# io1.net
KiCad netlist of a schematic drawn in EAGLE
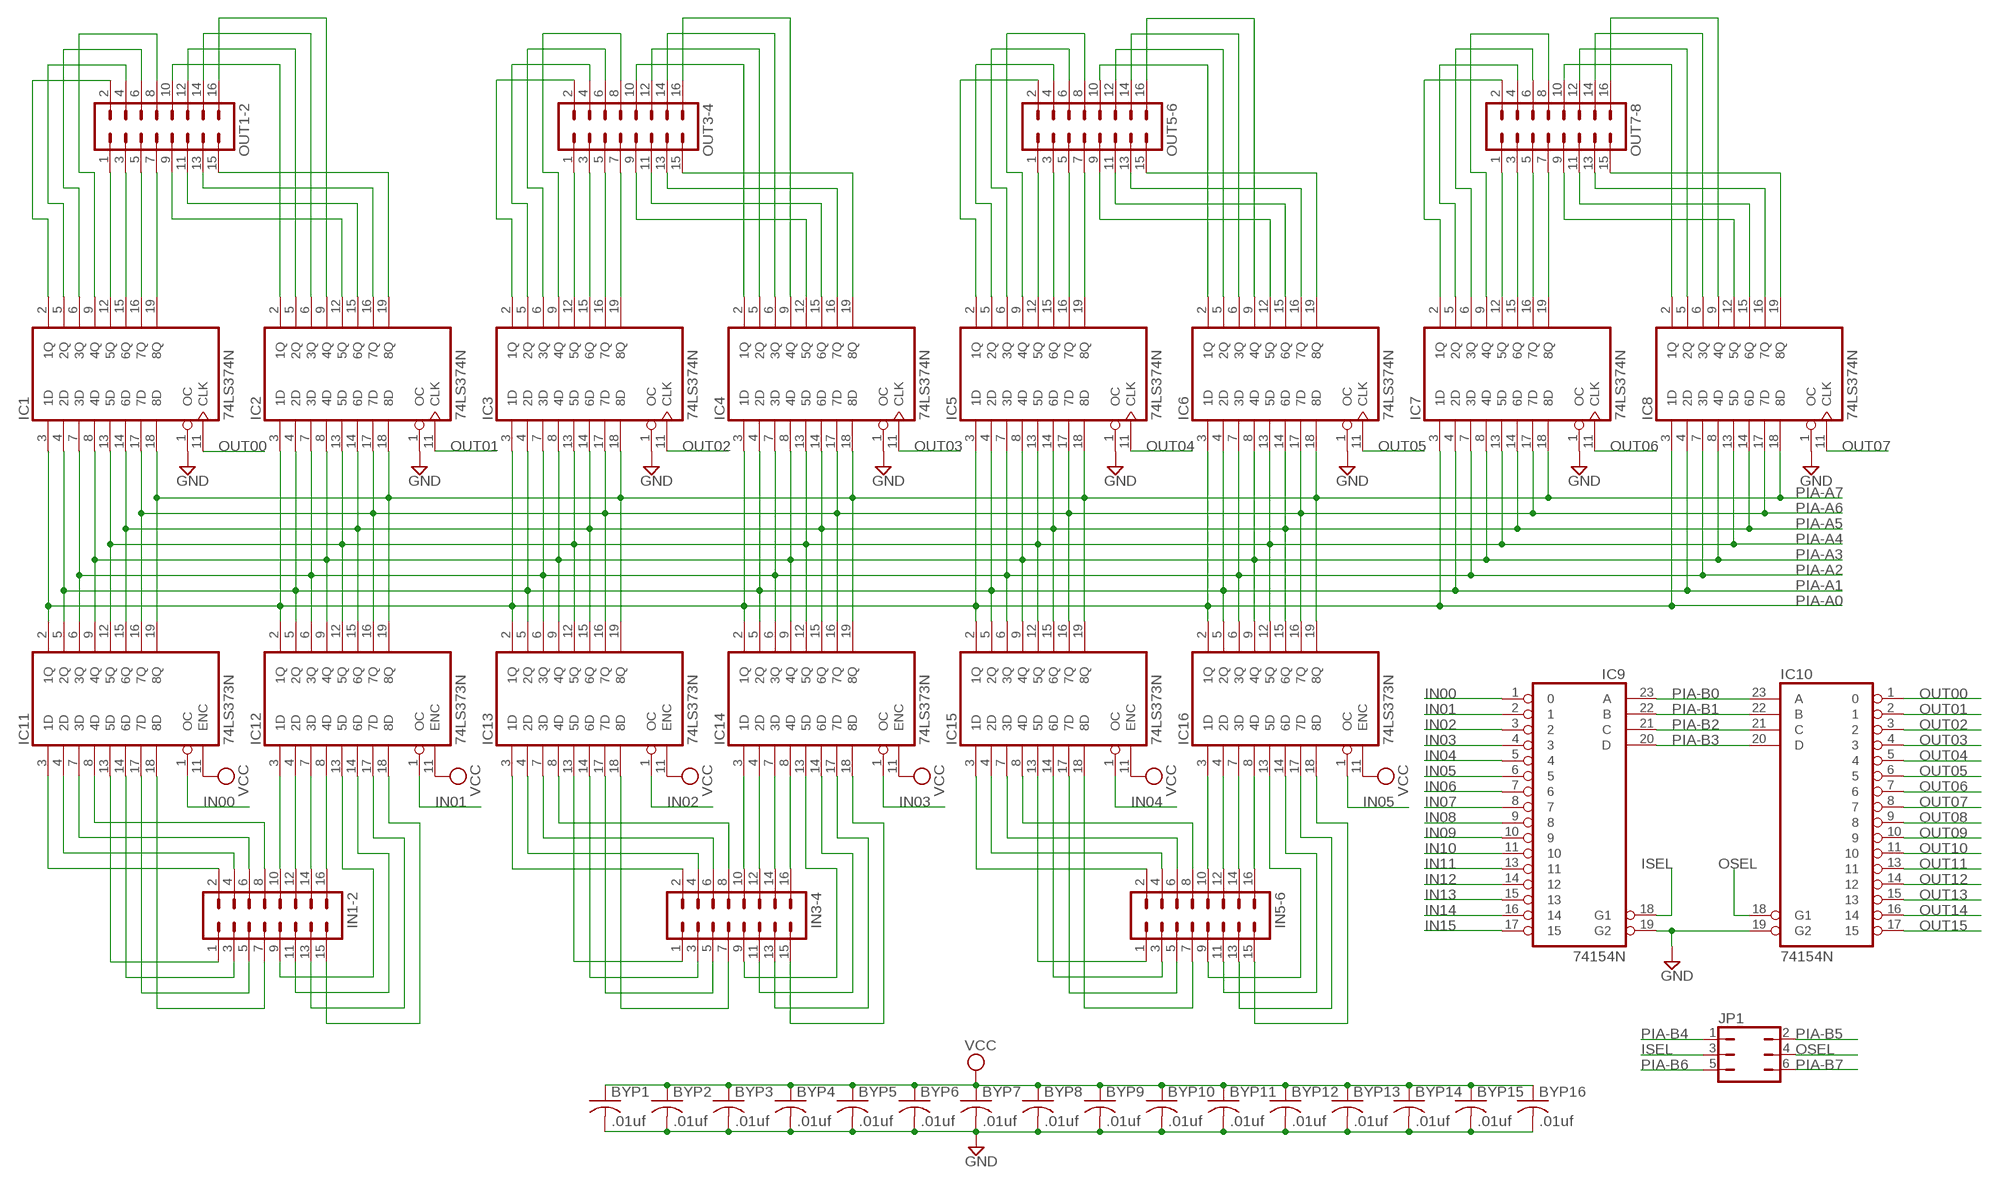
[diagram p0: schematic, sheet 1]
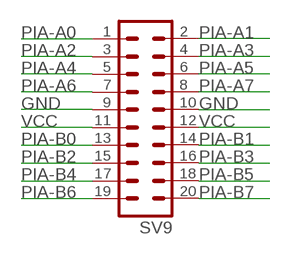
[diagram p1: schematic, sheet 2]

(export (version "E")
  (design (tool "Eeschema 10.0.6"))
  (components
    (comp (ref "SV9")
      (value "MA10-2")
      (footprint "eagle-import:MA10-2")
      (libsource (lib "eagle-import") (part "MA10-2"))
    )
    (comp (ref "BYP1")
      (value ".01uf")
      (footprint "eagle-import:C050-025X075")
      (libsource (lib "eagle-import") (part "C-US050-025X075"))
    )
    (comp (ref "BYP2")
      (value ".01uf")
      (footprint "eagle-import:C050-025X075")
      (libsource (lib "eagle-import") (part "C-US050-025X075"))
    )
    (comp (ref "BYP3")
      (value ".01uf")
      (footprint "eagle-import:C050-025X075")
      (libsource (lib "eagle-import") (part "C-US050-025X075"))
    )
    (comp (ref "BYP4")
      (value ".01uf")
      (footprint "eagle-import:C050-025X075")
      (libsource (lib "eagle-import") (part "C-US050-025X075"))
    )
    (comp (ref "BYP5")
      (value ".01uf")
      (footprint "eagle-import:C050-025X075")
      (libsource (lib "eagle-import") (part "C-US050-025X075"))
    )
    (comp (ref "BYP6")
      (value ".01uf")
      (footprint "eagle-import:C050-025X075")
      (libsource (lib "eagle-import") (part "C-US050-025X075"))
    )
    (comp (ref "BYP7")
      (value ".01uf")
      (footprint "eagle-import:C050-025X075")
      (libsource (lib "eagle-import") (part "C-US050-025X075"))
    )
    (comp (ref "BYP8")
      (value ".01uf")
      (footprint "eagle-import:C050-025X075")
      (libsource (lib "eagle-import") (part "C-US050-025X075"))
    )
    (comp (ref "BYP9")
      (value ".01uf")
      (footprint "eagle-import:C050-025X075")
      (libsource (lib "eagle-import") (part "C-US050-025X075"))
    )
    (comp (ref "BYP10")
      (value ".01uf")
      (footprint "eagle-import:C050-025X075")
      (libsource (lib "eagle-import") (part "C-US050-025X075"))
    )
    (comp (ref "BYP11")
      (value ".01uf")
      (footprint "eagle-import:C050-025X075")
      (libsource (lib "eagle-import") (part "C-US050-025X075"))
    )
    (comp (ref "BYP12")
      (value ".01uf")
      (footprint "eagle-import:C050-025X075")
      (libsource (lib "eagle-import") (part "C-US050-025X075"))
    )
    (comp (ref "BYP13")
      (value ".01uf")
      (footprint "eagle-import:C050-025X075")
      (libsource (lib "eagle-import") (part "C-US050-025X075"))
    )
    (comp (ref "BYP14")
      (value ".01uf")
      (footprint "eagle-import:C050-025X075")
      (libsource (lib "eagle-import") (part "C-US050-025X075"))
    )
    (comp (ref "BYP15")
      (value ".01uf")
      (footprint "eagle-import:C050-025X075")
      (libsource (lib "eagle-import") (part "C-US050-025X075"))
    )
    (comp (ref "BYP16")
      (value ".01uf")
      (footprint "eagle-import:C050-025X075")
      (libsource (lib "eagle-import") (part "C-US050-025X075"))
    )
    (comp (ref "IC1")
      (value "74LS374N")
      (footprint "eagle-import:DIL20")
      (libsource (lib "eagle-import") (part "74374NLS"))
    )
    (comp (ref "IC2")
      (value "74LS374N")
      (footprint "eagle-import:DIL20")
      (libsource (lib "eagle-import") (part "74374NLS"))
    )
    (comp (ref "IC3")
      (value "74LS374N")
      (footprint "eagle-import:DIL20")
      (libsource (lib "eagle-import") (part "74374NLS"))
    )
    (comp (ref "IC4")
      (value "74LS374N")
      (footprint "eagle-import:DIL20")
      (libsource (lib "eagle-import") (part "74374NLS"))
    )
    (comp (ref "IC5")
      (value "74LS374N")
      (footprint "eagle-import:DIL20")
      (libsource (lib "eagle-import") (part "74374NLS"))
    )
    (comp (ref "IC6")
      (value "74LS374N")
      (footprint "eagle-import:DIL20")
      (libsource (lib "eagle-import") (part "74374NLS"))
    )
    (comp (ref "IC7")
      (value "74LS374N")
      (footprint "eagle-import:DIL20")
      (libsource (lib "eagle-import") (part "74374NLS"))
    )
    (comp (ref "IC8")
      (value "74LS374N")
      (footprint "eagle-import:DIL20")
      (libsource (lib "eagle-import") (part "74374NLS"))
    )
    (comp (ref "IC9")
      (value "74154N")
      (footprint "eagle-import:DIL24-6")
      (libsource (lib "eagle-import") (part "74154N"))
    )
    (comp (ref "IC10")
      (value "74154N")
      (footprint "eagle-import:DIL24-6")
      (libsource (lib "eagle-import") (part "74154N"))
    )
    (comp (ref "IC11")
      (value "74LS373N")
      (footprint "eagle-import:DIL20")
      (libsource (lib "eagle-import") (part "74373NLS"))
    )
    (comp (ref "IC12")
      (value "74LS373N")
      (footprint "eagle-import:DIL20")
      (libsource (lib "eagle-import") (part "74373NLS"))
    )
    (comp (ref "IC13")
      (value "74LS373N")
      (footprint "eagle-import:DIL20")
      (libsource (lib "eagle-import") (part "74373NLS"))
    )
    (comp (ref "IC14")
      (value "74LS373N")
      (footprint "eagle-import:DIL20")
      (libsource (lib "eagle-import") (part "74373NLS"))
    )
    (comp (ref "IC15")
      (value "74LS373N")
      (footprint "eagle-import:DIL20")
      (libsource (lib "eagle-import") (part "74373NLS"))
    )
    (comp (ref "IC16")
      (value "74LS373N")
      (footprint "eagle-import:DIL20")
      (libsource (lib "eagle-import") (part "74373NLS"))
    )
    (comp (ref "IN1-2")
      (value "MA08-2")
      (footprint "eagle-import:MA08-2")
      (libsource (lib "eagle-import") (part "MA08-2"))
    )
    (comp (ref "IN3-4")
      (value "MA08-2")
      (footprint "eagle-import:MA08-2")
      (libsource (lib "eagle-import") (part "MA08-2"))
    )
    (comp (ref "IN5-6")
      (value "MA08-2")
      (footprint "eagle-import:MA08-2")
      (libsource (lib "eagle-import") (part "MA08-2"))
    )
    (comp (ref "JP1")
      (value "JP3Q")
      (footprint "eagle-import:JP3Q")
      (libsource (lib "eagle-import") (part "JP3Q"))
    )
    (comp (ref "OUT1-2")
      (value "MA08-2")
      (footprint "eagle-import:MA08-2")
      (libsource (lib "eagle-import") (part "MA08-2"))
    )
    (comp (ref "OUT3-4")
      (value "MA08-2")
      (footprint "eagle-import:MA08-2")
      (libsource (lib "eagle-import") (part "MA08-2"))
    )
    (comp (ref "OUT5-6")
      (value "MA08-2")
      (footprint "eagle-import:MA08-2")
      (libsource (lib "eagle-import") (part "MA08-2"))
    )
    (comp (ref "OUT7-8")
      (value "MA08-2")
      (footprint "eagle-import:MA08-2")
      (libsource (lib "eagle-import") (part "MA08-2"))
    )
  )
  (nets
    (net (code "1") (name "GND") (class "Default")
      (node (ref "BYP1") (pin "2") (pinfunction "2_2") (pintype "passive"))
      (node (ref "BYP10") (pin "2") (pinfunction "2_2") (pintype "passive"))
      (node (ref "BYP11") (pin "2") (pinfunction "2_2") (pintype "passive"))
      (node (ref "BYP12") (pin "2") (pinfunction "2_2") (pintype "passive"))
      (node (ref "BYP13") (pin "2") (pinfunction "2_2") (pintype "passive"))
      (node (ref "BYP14") (pin "2") (pinfunction "2_2") (pintype "passive"))
      (node (ref "BYP15") (pin "2") (pinfunction "2_2") (pintype "passive"))
      (node (ref "BYP16") (pin "2") (pinfunction "2_2") (pintype "passive"))
      (node (ref "BYP2") (pin "2") (pinfunction "2_2") (pintype "passive"))
      (node (ref "BYP3") (pin "2") (pinfunction "2_2") (pintype "passive"))
      (node (ref "BYP4") (pin "2") (pinfunction "2_2") (pintype "passive"))
      (node (ref "BYP5") (pin "2") (pinfunction "2_2") (pintype "passive"))
      (node (ref "BYP6") (pin "2") (pinfunction "2_2") (pintype "passive"))
      (node (ref "BYP7") (pin "2") (pinfunction "2_2") (pintype "passive"))
      (node (ref "BYP8") (pin "2") (pinfunction "2_2") (pintype "passive"))
      (node (ref "BYP9") (pin "2") (pinfunction "2_2") (pintype "passive"))
      (node (ref "IC1") (pin "1") (pinfunction "OC_1") (pintype "input"))
      (node (ref "IC10") (pin "19") (pinfunction "G2_19") (pintype "input"))
      (node (ref "IC2") (pin "1") (pinfunction "OC_1") (pintype "input"))
      (node (ref "IC3") (pin "1") (pinfunction "OC_1") (pintype "input"))
      (node (ref "IC4") (pin "1") (pinfunction "OC_1") (pintype "input"))
      (node (ref "IC5") (pin "1") (pinfunction "OC_1") (pintype "input"))
      (node (ref "IC6") (pin "1") (pinfunction "OC_1") (pintype "input"))
      (node (ref "IC7") (pin "1") (pinfunction "OC_1") (pintype "input"))
      (node (ref "IC8") (pin "1") (pinfunction "OC_1") (pintype "input"))
      (node (ref "IC9") (pin "19") (pinfunction "G2_19") (pintype "input"))
      (node (ref "SV9") (pin "10") (pinfunction "10_10") (pintype "passive"))
      (node (ref "SV9") (pin "9") (pinfunction "9_9") (pintype "passive"))
    )
    (net (code "2") (name "IN00") (class "Default")
      (node (ref "IC11") (pin "1") (pinfunction "OC_1") (pintype "input"))
      (node (ref "IC9") (pin "1") (pinfunction "0_1") (pintype "output"))
    )
    (net (code "3") (name "IN01") (class "Default")
      (node (ref "IC12") (pin "1") (pinfunction "OC_1") (pintype "input"))
      (node (ref "IC9") (pin "2") (pinfunction "1_2") (pintype "output"))
    )
    (net (code "4") (name "IN02") (class "Default")
      (node (ref "IC13") (pin "1") (pinfunction "OC_1") (pintype "input"))
      (node (ref "IC9") (pin "3") (pinfunction "2_3") (pintype "output"))
    )
    (net (code "5") (name "IN03") (class "Default")
      (node (ref "IC14") (pin "1") (pinfunction "OC_1") (pintype "input"))
      (node (ref "IC9") (pin "4") (pinfunction "3_4") (pintype "output"))
    )
    (net (code "6") (name "IN04") (class "Default")
      (node (ref "IC15") (pin "1") (pinfunction "OC_1") (pintype "input"))
      (node (ref "IC9") (pin "5") (pinfunction "4_5") (pintype "output"))
    )
    (net (code "7") (name "IN05") (class "Default")
      (node (ref "IC16") (pin "1") (pinfunction "OC_1") (pintype "input"))
      (node (ref "IC9") (pin "6") (pinfunction "5_6") (pintype "output"))
    )
    (net (code "8") (name "IN06") (class "Default")
      (node (ref "IC9") (pin "7") (pinfunction "6_7") (pintype "output"))
    )
    (net (code "9") (name "IN07") (class "Default")
      (node (ref "IC9") (pin "8") (pinfunction "7_8") (pintype "output"))
    )
    (net (code "10") (name "IN08") (class "Default")
      (node (ref "IC9") (pin "9") (pinfunction "8_9") (pintype "output"))
    )
    (net (code "11") (name "IN09") (class "Default")
      (node (ref "IC9") (pin "10") (pinfunction "9_10") (pintype "output"))
    )
    (net (code "12") (name "IN10") (class "Default")
      (node (ref "IC9") (pin "11") (pinfunction "10_11") (pintype "output"))
    )
    (net (code "13") (name "IN11") (class "Default")
      (node (ref "IC9") (pin "13") (pinfunction "11_13") (pintype "output"))
    )
    (net (code "14") (name "IN12") (class "Default")
      (node (ref "IC9") (pin "14") (pinfunction "12_14") (pintype "output"))
    )
    (net (code "15") (name "IN13") (class "Default")
      (node (ref "IC9") (pin "15") (pinfunction "13_15") (pintype "output"))
    )
    (net (code "16") (name "IN14") (class "Default")
      (node (ref "IC9") (pin "16") (pinfunction "14_16") (pintype "output"))
    )
    (net (code "17") (name "IN15") (class "Default")
      (node (ref "IC9") (pin "17") (pinfunction "15_17") (pintype "output"))
    )
    (net (code "18") (name "ISEL") (class "Default")
      (node (ref "IC9") (pin "18") (pinfunction "G1_18") (pintype "input"))
      (node (ref "JP1") (pin "3") (pinfunction "3_3") (pintype "passive"))
    )
    (net (code "19") (name "Net-(IC1A-1Q)") (class "Default")
      (node (ref "IC1") (pin "2") (pinfunction "1Q_2") (pintype "tri_state"))
      (node (ref "OUT1-2") (pin "2") (pinfunction "2_2") (pintype "passive"))
    )
    (net (code "20") (name "Net-(IC1A-2Q)") (class "Default")
      (node (ref "IC1") (pin "5") (pinfunction "2Q_5") (pintype "tri_state"))
      (node (ref "OUT1-2") (pin "4") (pinfunction "4_4") (pintype "passive"))
    )
    (net (code "21") (name "Net-(IC1A-3Q)") (class "Default")
      (node (ref "IC1") (pin "6") (pinfunction "3Q_6") (pintype "tri_state"))
      (node (ref "OUT1-2") (pin "6") (pinfunction "6_6") (pintype "passive"))
    )
    (net (code "22") (name "Net-(IC1A-4Q)") (class "Default")
      (node (ref "IC1") (pin "9") (pinfunction "4Q_9") (pintype "tri_state"))
      (node (ref "OUT1-2") (pin "8") (pinfunction "8_8") (pintype "passive"))
    )
    (net (code "23") (name "Net-(IC1A-5Q)") (class "Default")
      (node (ref "IC1") (pin "12") (pinfunction "5Q_12") (pintype "tri_state"))
      (node (ref "OUT1-2") (pin "1") (pinfunction "1_1") (pintype "passive"))
    )
    (net (code "24") (name "Net-(IC1A-6Q)") (class "Default")
      (node (ref "IC1") (pin "15") (pinfunction "6Q_15") (pintype "tri_state"))
      (node (ref "OUT1-2") (pin "3") (pinfunction "3_3") (pintype "passive"))
    )
    (net (code "25") (name "Net-(IC1A-7Q)") (class "Default")
      (node (ref "IC1") (pin "16") (pinfunction "7Q_16") (pintype "tri_state"))
      (node (ref "OUT1-2") (pin "5") (pinfunction "5_5") (pintype "passive"))
    )
    (net (code "26") (name "Net-(IC1A-8Q)") (class "Default")
      (node (ref "IC1") (pin "19") (pinfunction "8Q_19") (pintype "tri_state"))
      (node (ref "OUT1-2") (pin "7") (pinfunction "7_7") (pintype "passive"))
    )
    (net (code "27") (name "Net-(IC2A-1Q)") (class "Default")
      (node (ref "IC2") (pin "2") (pinfunction "1Q_2") (pintype "tri_state"))
      (node (ref "OUT1-2") (pin "10") (pinfunction "10_10") (pintype "passive"))
    )
    (net (code "28") (name "Net-(IC2A-2Q)") (class "Default")
      (node (ref "IC2") (pin "5") (pinfunction "2Q_5") (pintype "tri_state"))
      (node (ref "OUT1-2") (pin "12") (pinfunction "12_12") (pintype "passive"))
    )
    (net (code "29") (name "Net-(IC2A-3Q)") (class "Default")
      (node (ref "IC2") (pin "6") (pinfunction "3Q_6") (pintype "tri_state"))
      (node (ref "OUT1-2") (pin "14") (pinfunction "14_14") (pintype "passive"))
    )
    (net (code "30") (name "Net-(IC2A-4Q)") (class "Default")
      (node (ref "IC2") (pin "9") (pinfunction "4Q_9") (pintype "tri_state"))
      (node (ref "OUT1-2") (pin "16") (pinfunction "16_16") (pintype "passive"))
    )
    (net (code "31") (name "Net-(IC2A-5Q)") (class "Default")
      (node (ref "IC2") (pin "12") (pinfunction "5Q_12") (pintype "tri_state"))
      (node (ref "OUT1-2") (pin "9") (pinfunction "9_9") (pintype "passive"))
    )
    (net (code "32") (name "Net-(IC2A-6Q)") (class "Default")
      (node (ref "IC2") (pin "15") (pinfunction "6Q_15") (pintype "tri_state"))
      (node (ref "OUT1-2") (pin "11") (pinfunction "11_11") (pintype "passive"))
    )
    (net (code "33") (name "Net-(IC2A-7Q)") (class "Default")
      (node (ref "IC2") (pin "16") (pinfunction "7Q_16") (pintype "tri_state"))
      (node (ref "OUT1-2") (pin "13") (pinfunction "13_13") (pintype "passive"))
    )
    (net (code "34") (name "Net-(IC2A-8Q)") (class "Default")
      (node (ref "IC2") (pin "19") (pinfunction "8Q_19") (pintype "tri_state"))
      (node (ref "OUT1-2") (pin "15") (pinfunction "15_15") (pintype "passive"))
    )
    (net (code "35") (name "Net-(IC3A-1Q)") (class "Default")
      (node (ref "IC3") (pin "2") (pinfunction "1Q_2") (pintype "tri_state"))
      (node (ref "OUT3-4") (pin "2") (pinfunction "2_2") (pintype "passive"))
    )
    (net (code "36") (name "Net-(IC3A-2Q)") (class "Default")
      (node (ref "IC3") (pin "5") (pinfunction "2Q_5") (pintype "tri_state"))
      (node (ref "OUT3-4") (pin "4") (pinfunction "4_4") (pintype "passive"))
    )
    (net (code "37") (name "Net-(IC3A-3Q)") (class "Default")
      (node (ref "IC3") (pin "6") (pinfunction "3Q_6") (pintype "tri_state"))
      (node (ref "OUT3-4") (pin "6") (pinfunction "6_6") (pintype "passive"))
    )
    (net (code "38") (name "Net-(IC3A-4Q)") (class "Default")
      (node (ref "IC3") (pin "9") (pinfunction "4Q_9") (pintype "tri_state"))
      (node (ref "OUT3-4") (pin "8") (pinfunction "8_8") (pintype "passive"))
    )
    (net (code "39") (name "Net-(IC3A-5Q)") (class "Default")
      (node (ref "IC3") (pin "12") (pinfunction "5Q_12") (pintype "tri_state"))
      (node (ref "OUT3-4") (pin "1") (pinfunction "1_1") (pintype "passive"))
    )
    (net (code "40") (name "Net-(IC3A-6Q)") (class "Default")
      (node (ref "IC3") (pin "15") (pinfunction "6Q_15") (pintype "tri_state"))
      (node (ref "OUT3-4") (pin "3") (pinfunction "3_3") (pintype "passive"))
    )
    (net (code "41") (name "Net-(IC3A-7Q)") (class "Default")
      (node (ref "IC3") (pin "16") (pinfunction "7Q_16") (pintype "tri_state"))
      (node (ref "OUT3-4") (pin "5") (pinfunction "5_5") (pintype "passive"))
    )
    (net (code "42") (name "Net-(IC3A-8Q)") (class "Default")
      (node (ref "IC3") (pin "19") (pinfunction "8Q_19") (pintype "tri_state"))
      (node (ref "OUT3-4") (pin "7") (pinfunction "7_7") (pintype "passive"))
    )
    (net (code "43") (name "Net-(IC4A-1Q)") (class "Default")
      (node (ref "IC4") (pin "2") (pinfunction "1Q_2") (pintype "tri_state"))
      (node (ref "OUT3-4") (pin "10") (pinfunction "10_10") (pintype "passive"))
    )
    (net (code "44") (name "Net-(IC4A-2Q)") (class "Default")
      (node (ref "IC4") (pin "5") (pinfunction "2Q_5") (pintype "tri_state"))
      (node (ref "OUT3-4") (pin "12") (pinfunction "12_12") (pintype "passive"))
    )
    (net (code "45") (name "Net-(IC4A-3Q)") (class "Default")
      (node (ref "IC4") (pin "6") (pinfunction "3Q_6") (pintype "tri_state"))
      (node (ref "OUT3-4") (pin "14") (pinfunction "14_14") (pintype "passive"))
    )
    (net (code "46") (name "Net-(IC4A-4Q)") (class "Default")
      (node (ref "IC4") (pin "9") (pinfunction "4Q_9") (pintype "tri_state"))
      (node (ref "OUT3-4") (pin "16") (pinfunction "16_16") (pintype "passive"))
    )
    (net (code "47") (name "Net-(IC4A-5Q)") (class "Default")
      (node (ref "IC4") (pin "12") (pinfunction "5Q_12") (pintype "tri_state"))
      (node (ref "OUT3-4") (pin "9") (pinfunction "9_9") (pintype "passive"))
    )
    (net (code "48") (name "Net-(IC4A-6Q)") (class "Default")
      (node (ref "IC4") (pin "15") (pinfunction "6Q_15") (pintype "tri_state"))
      (node (ref "OUT3-4") (pin "11") (pinfunction "11_11") (pintype "passive"))
    )
    (net (code "49") (name "Net-(IC4A-7Q)") (class "Default")
      (node (ref "IC4") (pin "16") (pinfunction "7Q_16") (pintype "tri_state"))
      (node (ref "OUT3-4") (pin "13") (pinfunction "13_13") (pintype "passive"))
    )
    (net (code "50") (name "Net-(IC4A-8Q)") (class "Default")
      (node (ref "IC4") (pin "19") (pinfunction "8Q_19") (pintype "tri_state"))
      (node (ref "OUT3-4") (pin "15") (pinfunction "15_15") (pintype "passive"))
    )
    (net (code "51") (name "Net-(IC5A-1Q)") (class "Default")
      (node (ref "IC5") (pin "2") (pinfunction "1Q_2") (pintype "tri_state"))
      (node (ref "OUT5-6") (pin "2") (pinfunction "2_2") (pintype "passive"))
    )
    (net (code "52") (name "Net-(IC5A-2Q)") (class "Default")
      (node (ref "IC5") (pin "5") (pinfunction "2Q_5") (pintype "tri_state"))
      (node (ref "OUT5-6") (pin "4") (pinfunction "4_4") (pintype "passive"))
    )
    (net (code "53") (name "Net-(IC5A-3Q)") (class "Default")
      (node (ref "IC5") (pin "6") (pinfunction "3Q_6") (pintype "tri_state"))
      (node (ref "OUT5-6") (pin "6") (pinfunction "6_6") (pintype "passive"))
    )
    (net (code "54") (name "Net-(IC5A-4Q)") (class "Default")
      (node (ref "IC5") (pin "9") (pinfunction "4Q_9") (pintype "tri_state"))
      (node (ref "OUT5-6") (pin "8") (pinfunction "8_8") (pintype "passive"))
    )
    (net (code "55") (name "Net-(IC5A-5Q)") (class "Default")
      (node (ref "IC5") (pin "12") (pinfunction "5Q_12") (pintype "tri_state"))
      (node (ref "OUT5-6") (pin "1") (pinfunction "1_1") (pintype "passive"))
    )
    (net (code "56") (name "Net-(IC5A-6Q)") (class "Default")
      (node (ref "IC5") (pin "15") (pinfunction "6Q_15") (pintype "tri_state"))
      (node (ref "OUT5-6") (pin "3") (pinfunction "3_3") (pintype "passive"))
    )
    (net (code "57") (name "Net-(IC5A-7Q)") (class "Default")
      (node (ref "IC5") (pin "16") (pinfunction "7Q_16") (pintype "tri_state"))
      (node (ref "OUT5-6") (pin "5") (pinfunction "5_5") (pintype "passive"))
    )
    (net (code "58") (name "Net-(IC5A-8Q)") (class "Default")
      (node (ref "IC5") (pin "19") (pinfunction "8Q_19") (pintype "tri_state"))
      (node (ref "OUT5-6") (pin "7") (pinfunction "7_7") (pintype "passive"))
    )
    (net (code "59") (name "Net-(IC6A-1Q)") (class "Default")
      (node (ref "IC6") (pin "2") (pinfunction "1Q_2") (pintype "tri_state"))
      (node (ref "OUT5-6") (pin "10") (pinfunction "10_10") (pintype "passive"))
    )
    (net (code "60") (name "Net-(IC6A-2Q)") (class "Default")
      (node (ref "IC6") (pin "5") (pinfunction "2Q_5") (pintype "tri_state"))
      (node (ref "OUT5-6") (pin "12") (pinfunction "12_12") (pintype "passive"))
    )
    (net (code "61") (name "Net-(IC6A-3Q)") (class "Default")
      (node (ref "IC6") (pin "6") (pinfunction "3Q_6") (pintype "tri_state"))
      (node (ref "OUT5-6") (pin "14") (pinfunction "14_14") (pintype "passive"))
    )
    (net (code "62") (name "Net-(IC6A-4Q)") (class "Default")
      (node (ref "IC6") (pin "9") (pinfunction "4Q_9") (pintype "tri_state"))
      (node (ref "OUT5-6") (pin "16") (pinfunction "16_16") (pintype "passive"))
    )
    (net (code "63") (name "Net-(IC6A-5Q)") (class "Default")
      (node (ref "IC6") (pin "12") (pinfunction "5Q_12") (pintype "tri_state"))
      (node (ref "OUT5-6") (pin "9") (pinfunction "9_9") (pintype "passive"))
    )
    (net (code "64") (name "Net-(IC6A-6Q)") (class "Default")
      (node (ref "IC6") (pin "15") (pinfunction "6Q_15") (pintype "tri_state"))
      (node (ref "OUT5-6") (pin "11") (pinfunction "11_11") (pintype "passive"))
    )
    (net (code "65") (name "Net-(IC6A-7Q)") (class "Default")
      (node (ref "IC6") (pin "16") (pinfunction "7Q_16") (pintype "tri_state"))
      (node (ref "OUT5-6") (pin "13") (pinfunction "13_13") (pintype "passive"))
    )
    (net (code "66") (name "Net-(IC6A-8Q)") (class "Default")
      (node (ref "IC6") (pin "19") (pinfunction "8Q_19") (pintype "tri_state"))
      (node (ref "OUT5-6") (pin "15") (pinfunction "15_15") (pintype "passive"))
    )
    (net (code "67") (name "Net-(IC7A-1Q)") (class "Default")
      (node (ref "IC7") (pin "2") (pinfunction "1Q_2") (pintype "tri_state"))
      (node (ref "OUT7-8") (pin "2") (pinfunction "2_2") (pintype "passive"))
    )
    (net (code "68") (name "Net-(IC7A-2Q)") (class "Default")
      (node (ref "IC7") (pin "5") (pinfunction "2Q_5") (pintype "tri_state"))
      (node (ref "OUT7-8") (pin "4") (pinfunction "4_4") (pintype "passive"))
    )
    (net (code "69") (name "Net-(IC7A-3Q)") (class "Default")
      (node (ref "IC7") (pin "6") (pinfunction "3Q_6") (pintype "tri_state"))
      (node (ref "OUT7-8") (pin "6") (pinfunction "6_6") (pintype "passive"))
    )
    (net (code "70") (name "Net-(IC7A-4Q)") (class "Default")
      (node (ref "IC7") (pin "9") (pinfunction "4Q_9") (pintype "tri_state"))
      (node (ref "OUT7-8") (pin "8") (pinfunction "8_8") (pintype "passive"))
    )
    (net (code "71") (name "Net-(IC7A-5Q)") (class "Default")
      (node (ref "IC7") (pin "12") (pinfunction "5Q_12") (pintype "tri_state"))
      (node (ref "OUT7-8") (pin "1") (pinfunction "1_1") (pintype "passive"))
    )
    (net (code "72") (name "Net-(IC7A-6Q)") (class "Default")
      (node (ref "IC7") (pin "15") (pinfunction "6Q_15") (pintype "tri_state"))
      (node (ref "OUT7-8") (pin "3") (pinfunction "3_3") (pintype "passive"))
    )
    (net (code "73") (name "Net-(IC7A-7Q)") (class "Default")
      (node (ref "IC7") (pin "16") (pinfunction "7Q_16") (pintype "tri_state"))
      (node (ref "OUT7-8") (pin "5") (pinfunction "5_5") (pintype "passive"))
    )
    (net (code "74") (name "Net-(IC7A-8Q)") (class "Default")
      (node (ref "IC7") (pin "19") (pinfunction "8Q_19") (pintype "tri_state"))
      (node (ref "OUT7-8") (pin "7") (pinfunction "7_7") (pintype "passive"))
    )
    (net (code "75") (name "Net-(IC8A-1Q)") (class "Default")
      (node (ref "IC8") (pin "2") (pinfunction "1Q_2") (pintype "tri_state"))
      (node (ref "OUT7-8") (pin "10") (pinfunction "10_10") (pintype "passive"))
    )
    (net (code "76") (name "Net-(IC8A-2Q)") (class "Default")
      (node (ref "IC8") (pin "5") (pinfunction "2Q_5") (pintype "tri_state"))
      (node (ref "OUT7-8") (pin "12") (pinfunction "12_12") (pintype "passive"))
    )
    (net (code "77") (name "Net-(IC8A-3Q)") (class "Default")
      (node (ref "IC8") (pin "6") (pinfunction "3Q_6") (pintype "tri_state"))
      (node (ref "OUT7-8") (pin "14") (pinfunction "14_14") (pintype "passive"))
    )
    (net (code "78") (name "Net-(IC8A-4Q)") (class "Default")
      (node (ref "IC8") (pin "9") (pinfunction "4Q_9") (pintype "tri_state"))
      (node (ref "OUT7-8") (pin "16") (pinfunction "16_16") (pintype "passive"))
    )
    (net (code "79") (name "Net-(IC8A-5Q)") (class "Default")
      (node (ref "IC8") (pin "12") (pinfunction "5Q_12") (pintype "tri_state"))
      (node (ref "OUT7-8") (pin "9") (pinfunction "9_9") (pintype "passive"))
    )
    (net (code "80") (name "Net-(IC8A-6Q)") (class "Default")
      (node (ref "IC8") (pin "15") (pinfunction "6Q_15") (pintype "tri_state"))
      (node (ref "OUT7-8") (pin "11") (pinfunction "11_11") (pintype "passive"))
    )
    (net (code "81") (name "Net-(IC8A-7Q)") (class "Default")
      (node (ref "IC8") (pin "16") (pinfunction "7Q_16") (pintype "tri_state"))
      (node (ref "OUT7-8") (pin "13") (pinfunction "13_13") (pintype "passive"))
    )
    (net (code "82") (name "Net-(IC8A-8Q)") (class "Default")
      (node (ref "IC8") (pin "19") (pinfunction "8Q_19") (pintype "tri_state"))
      (node (ref "OUT7-8") (pin "15") (pinfunction "15_15") (pintype "passive"))
    )
    (net (code "83") (name "Net-(IC11A-1D)") (class "Default")
      (node (ref "IC11") (pin "3") (pinfunction "1D_3") (pintype "input"))
      (node (ref "IN1-2") (pin "2") (pinfunction "2_2") (pintype "passive"))
    )
    (net (code "84") (name "Net-(IC11A-2D)") (class "Default")
      (node (ref "IC11") (pin "4") (pinfunction "2D_4") (pintype "input"))
      (node (ref "IN1-2") (pin "4") (pinfunction "4_4") (pintype "passive"))
    )
    (net (code "85") (name "Net-(IC11A-3D)") (class "Default")
      (node (ref "IC11") (pin "7") (pinfunction "3D_7") (pintype "input"))
      (node (ref "IN1-2") (pin "6") (pinfunction "6_6") (pintype "passive"))
    )
    (net (code "86") (name "Net-(IC11A-4D)") (class "Default")
      (node (ref "IC11") (pin "8") (pinfunction "4D_8") (pintype "input"))
      (node (ref "IN1-2") (pin "8") (pinfunction "8_8") (pintype "passive"))
    )
    (net (code "87") (name "Net-(IC11A-5D)") (class "Default")
      (node (ref "IC11") (pin "13") (pinfunction "5D_13") (pintype "input"))
      (node (ref "IN1-2") (pin "1") (pinfunction "1_1") (pintype "passive"))
    )
    (net (code "88") (name "Net-(IC11A-6D)") (class "Default")
      (node (ref "IC11") (pin "14") (pinfunction "6D_14") (pintype "input"))
      (node (ref "IN1-2") (pin "3") (pinfunction "3_3") (pintype "passive"))
    )
    (net (code "89") (name "Net-(IC11A-7D)") (class "Default")
      (node (ref "IC11") (pin "17") (pinfunction "7D_17") (pintype "input"))
      (node (ref "IN1-2") (pin "5") (pinfunction "5_5") (pintype "passive"))
    )
    (net (code "90") (name "Net-(IC11A-8D)") (class "Default")
      (node (ref "IC11") (pin "18") (pinfunction "8D_18") (pintype "input"))
      (node (ref "IN1-2") (pin "7") (pinfunction "7_7") (pintype "passive"))
    )
    (net (code "91") (name "Net-(IC12A-1D)") (class "Default")
      (node (ref "IC12") (pin "3") (pinfunction "1D_3") (pintype "input"))
      (node (ref "IN1-2") (pin "10") (pinfunction "10_10") (pintype "passive"))
    )
    (net (code "92") (name "Net-(IC12A-2D)") (class "Default")
      (node (ref "IC12") (pin "4") (pinfunction "2D_4") (pintype "input"))
      (node (ref "IN1-2") (pin "12") (pinfunction "12_12") (pintype "passive"))
    )
    (net (code "93") (name "Net-(IC12A-3D)") (class "Default")
      (node (ref "IC12") (pin "7") (pinfunction "3D_7") (pintype "input"))
      (node (ref "IN1-2") (pin "14") (pinfunction "14_14") (pintype "passive"))
    )
    (net (code "94") (name "Net-(IC12A-4D)") (class "Default")
      (node (ref "IC12") (pin "8") (pinfunction "4D_8") (pintype "input"))
      (node (ref "IN1-2") (pin "16") (pinfunction "16_16") (pintype "passive"))
    )
    (net (code "95") (name "Net-(IC12A-5D)") (class "Default")
      (node (ref "IC12") (pin "13") (pinfunction "5D_13") (pintype "input"))
      (node (ref "IN1-2") (pin "9") (pinfunction "9_9") (pintype "passive"))
    )
    (net (code "96") (name "Net-(IC12A-6D)") (class "Default")
      (node (ref "IC12") (pin "14") (pinfunction "6D_14") (pintype "input"))
      (node (ref "IN1-2") (pin "11") (pinfunction "11_11") (pintype "passive"))
    )
    (net (code "97") (name "Net-(IC12A-7D)") (class "Default")
      (node (ref "IC12") (pin "17") (pinfunction "7D_17") (pintype "input"))
      (node (ref "IN1-2") (pin "13") (pinfunction "13_13") (pintype "passive"))
    )
    (net (code "98") (name "Net-(IC12A-8D)") (class "Default")
      (node (ref "IC12") (pin "18") (pinfunction "8D_18") (pintype "input"))
      (node (ref "IN1-2") (pin "15") (pinfunction "15_15") (pintype "passive"))
    )
    (net (code "99") (name "Net-(IC13A-1D)") (class "Default")
      (node (ref "IC13") (pin "3") (pinfunction "1D_3") (pintype "input"))
      (node (ref "IN3-4") (pin "2") (pinfunction "2_2") (pintype "passive"))
    )
    (net (code "100") (name "Net-(IC13A-2D)") (class "Default")
      (node (ref "IC13") (pin "4") (pinfunction "2D_4") (pintype "input"))
      (node (ref "IN3-4") (pin "4") (pinfunction "4_4") (pintype "passive"))
    )
    (net (code "101") (name "Net-(IC13A-3D)") (class "Default")
      (node (ref "IC13") (pin "7") (pinfunction "3D_7") (pintype "input"))
      (node (ref "IN3-4") (pin "6") (pinfunction "6_6") (pintype "passive"))
    )
    (net (code "102") (name "Net-(IC13A-4D)") (class "Default")
      (node (ref "IC13") (pin "8") (pinfunction "4D_8") (pintype "input"))
      (node (ref "IN3-4") (pin "8") (pinfunction "8_8") (pintype "passive"))
    )
    (net (code "103") (name "Net-(IC13A-5D)") (class "Default")
      (node (ref "IC13") (pin "13") (pinfunction "5D_13") (pintype "input"))
      (node (ref "IN3-4") (pin "1") (pinfunction "1_1") (pintype "passive"))
    )
    (net (code "104") (name "Net-(IC13A-6D)") (class "Default")
      (node (ref "IC13") (pin "14") (pinfunction "6D_14") (pintype "input"))
      (node (ref "IN3-4") (pin "3") (pinfunction "3_3") (pintype "passive"))
    )
    (net (code "105") (name "Net-(IC13A-7D)") (class "Default")
      (node (ref "IC13") (pin "17") (pinfunction "7D_17") (pintype "input"))
      (node (ref "IN3-4") (pin "5") (pinfunction "5_5") (pintype "passive"))
    )
    (net (code "106") (name "Net-(IC13A-8D)") (class "Default")
      (node (ref "IC13") (pin "18") (pinfunction "8D_18") (pintype "input"))
      (node (ref "IN3-4") (pin "7") (pinfunction "7_7") (pintype "passive"))
    )
    (net (code "107") (name "Net-(IC14A-1D)") (class "Default")
      (node (ref "IC14") (pin "3") (pinfunction "1D_3") (pintype "input"))
      (node (ref "IN3-4") (pin "10") (pinfunction "10_10") (pintype "passive"))
    )
    (net (code "108") (name "Net-(IC14A-2D)") (class "Default")
      (node (ref "IC14") (pin "4") (pinfunction "2D_4") (pintype "input"))
      (node (ref "IN3-4") (pin "12") (pinfunction "12_12") (pintype "passive"))
    )
    (net (code "109") (name "Net-(IC14A-3D)") (class "Default")
      (node (ref "IC14") (pin "7") (pinfunction "3D_7") (pintype "input"))
      (node (ref "IN3-4") (pin "14") (pinfunction "14_14") (pintype "passive"))
    )
    (net (code "110") (name "Net-(IC14A-4D)") (class "Default")
      (node (ref "IC14") (pin "8") (pinfunction "4D_8") (pintype "input"))
      (node (ref "IN3-4") (pin "16") (pinfunction "16_16") (pintype "passive"))
    )
    (net (code "111") (name "Net-(IC14A-5D)") (class "Default")
      (node (ref "IC14") (pin "13") (pinfunction "5D_13") (pintype "input"))
      (node (ref "IN3-4") (pin "9") (pinfunction "9_9") (pintype "passive"))
    )
    (net (code "112") (name "Net-(IC14A-6D)") (class "Default")
      (node (ref "IC14") (pin "14") (pinfunction "6D_14") (pintype "input"))
      (node (ref "IN3-4") (pin "11") (pinfunction "11_11") (pintype "passive"))
    )
    (net (code "113") (name "Net-(IC14A-7D)") (class "Default")
      (node (ref "IC14") (pin "17") (pinfunction "7D_17") (pintype "input"))
      (node (ref "IN3-4") (pin "13") (pinfunction "13_13") (pintype "passive"))
    )
    (net (code "114") (name "Net-(IC14A-8D)") (class "Default")
      (node (ref "IC14") (pin "18") (pinfunction "8D_18") (pintype "input"))
      (node (ref "IN3-4") (pin "15") (pinfunction "15_15") (pintype "passive"))
    )
    (net (code "115") (name "Net-(IC15A-1D)") (class "Default")
      (node (ref "IC15") (pin "3") (pinfunction "1D_3") (pintype "input"))
      (node (ref "IN5-6") (pin "2") (pinfunction "2_2") (pintype "passive"))
    )
    (net (code "116") (name "Net-(IC15A-2D)") (class "Default")
      (node (ref "IC15") (pin "4") (pinfunction "2D_4") (pintype "input"))
      (node (ref "IN5-6") (pin "4") (pinfunction "4_4") (pintype "passive"))
    )
    (net (code "117") (name "Net-(IC15A-3D)") (class "Default")
      (node (ref "IC15") (pin "7") (pinfunction "3D_7") (pintype "input"))
      (node (ref "IN5-6") (pin "6") (pinfunction "6_6") (pintype "passive"))
    )
    (net (code "118") (name "Net-(IC15A-4D)") (class "Default")
      (node (ref "IC15") (pin "8") (pinfunction "4D_8") (pintype "input"))
      (node (ref "IN5-6") (pin "8") (pinfunction "8_8") (pintype "passive"))
    )
    (net (code "119") (name "Net-(IC15A-5D)") (class "Default")
      (node (ref "IC15") (pin "13") (pinfunction "5D_13") (pintype "input"))
      (node (ref "IN5-6") (pin "1") (pinfunction "1_1") (pintype "passive"))
    )
    (net (code "120") (name "Net-(IC15A-6D)") (class "Default")
      (node (ref "IC15") (pin "14") (pinfunction "6D_14") (pintype "input"))
      (node (ref "IN5-6") (pin "3") (pinfunction "3_3") (pintype "passive"))
    )
    (net (code "121") (name "Net-(IC15A-7D)") (class "Default")
      (node (ref "IC15") (pin "17") (pinfunction "7D_17") (pintype "input"))
      (node (ref "IN5-6") (pin "5") (pinfunction "5_5") (pintype "passive"))
    )
    (net (code "122") (name "Net-(IC15A-8D)") (class "Default")
      (node (ref "IC15") (pin "18") (pinfunction "8D_18") (pintype "input"))
      (node (ref "IN5-6") (pin "7") (pinfunction "7_7") (pintype "passive"))
    )
    (net (code "123") (name "Net-(IC16A-1D)") (class "Default")
      (node (ref "IC16") (pin "3") (pinfunction "1D_3") (pintype "input"))
      (node (ref "IN5-6") (pin "10") (pinfunction "10_10") (pintype "passive"))
    )
    (net (code "124") (name "Net-(IC16A-2D)") (class "Default")
      (node (ref "IC16") (pin "4") (pinfunction "2D_4") (pintype "input"))
      (node (ref "IN5-6") (pin "12") (pinfunction "12_12") (pintype "passive"))
    )
    (net (code "125") (name "Net-(IC16A-3D)") (class "Default")
      (node (ref "IC16") (pin "7") (pinfunction "3D_7") (pintype "input"))
      (node (ref "IN5-6") (pin "14") (pinfunction "14_14") (pintype "passive"))
    )
    (net (code "126") (name "Net-(IC16A-4D)") (class "Default")
      (node (ref "IC16") (pin "8") (pinfunction "4D_8") (pintype "input"))
      (node (ref "IN5-6") (pin "16") (pinfunction "16_16") (pintype "passive"))
    )
    (net (code "127") (name "Net-(IC16A-5D)") (class "Default")
      (node (ref "IC16") (pin "13") (pinfunction "5D_13") (pintype "input"))
      (node (ref "IN5-6") (pin "9") (pinfunction "9_9") (pintype "passive"))
    )
    (net (code "128") (name "Net-(IC16A-6D)") (class "Default")
      (node (ref "IC16") (pin "14") (pinfunction "6D_14") (pintype "input"))
      (node (ref "IN5-6") (pin "11") (pinfunction "11_11") (pintype "passive"))
    )
    (net (code "129") (name "Net-(IC16A-7D)") (class "Default")
      (node (ref "IC16") (pin "17") (pinfunction "7D_17") (pintype "input"))
      (node (ref "IN5-6") (pin "13") (pinfunction "13_13") (pintype "passive"))
    )
    (net (code "130") (name "Net-(IC16A-8D)") (class "Default")
      (node (ref "IC16") (pin "18") (pinfunction "8D_18") (pintype "input"))
      (node (ref "IN5-6") (pin "15") (pinfunction "15_15") (pintype "passive"))
    )
    (net (code "131") (name "OSEL") (class "Default")
      (node (ref "IC10") (pin "18") (pinfunction "G1_18") (pintype "input"))
      (node (ref "JP1") (pin "4") (pinfunction "4_4") (pintype "passive"))
    )
    (net (code "132") (name "OUT00") (class "Default")
      (node (ref "IC1") (pin "11") (pinfunction "CLK_11") (pintype "input"))
      (node (ref "IC10") (pin "1") (pinfunction "0_1") (pintype "output"))
    )
    (net (code "133") (name "OUT01") (class "Default")
      (node (ref "IC10") (pin "2") (pinfunction "1_2") (pintype "output"))
      (node (ref "IC2") (pin "11") (pinfunction "CLK_11") (pintype "input"))
    )
    (net (code "134") (name "OUT02") (class "Default")
      (node (ref "IC10") (pin "3") (pinfunction "2_3") (pintype "output"))
      (node (ref "IC3") (pin "11") (pinfunction "CLK_11") (pintype "input"))
    )
    (net (code "135") (name "OUT03") (class "Default")
      (node (ref "IC10") (pin "4") (pinfunction "3_4") (pintype "output"))
      (node (ref "IC4") (pin "11") (pinfunction "CLK_11") (pintype "input"))
    )
    (net (code "136") (name "OUT04") (class "Default")
      (node (ref "IC10") (pin "5") (pinfunction "4_5") (pintype "output"))
      (node (ref "IC5") (pin "11") (pinfunction "CLK_11") (pintype "input"))
    )
    (net (code "137") (name "OUT05") (class "Default")
      (node (ref "IC10") (pin "6") (pinfunction "5_6") (pintype "output"))
      (node (ref "IC6") (pin "11") (pinfunction "CLK_11") (pintype "input"))
    )
    (net (code "138") (name "OUT06") (class "Default")
      (node (ref "IC10") (pin "7") (pinfunction "6_7") (pintype "output"))
      (node (ref "IC7") (pin "11") (pinfunction "CLK_11") (pintype "input"))
    )
    (net (code "139") (name "OUT07") (class "Default")
      (node (ref "IC10") (pin "8") (pinfunction "7_8") (pintype "output"))
      (node (ref "IC8") (pin "11") (pinfunction "CLK_11") (pintype "input"))
    )
    (net (code "140") (name "OUT08") (class "Default")
      (node (ref "IC10") (pin "9") (pinfunction "8_9") (pintype "output"))
    )
    (net (code "141") (name "OUT09") (class "Default")
      (node (ref "IC10") (pin "10") (pinfunction "9_10") (pintype "output"))
    )
    (net (code "142") (name "OUT10") (class "Default")
      (node (ref "IC10") (pin "11") (pinfunction "10_11") (pintype "output"))
    )
    (net (code "143") (name "OUT11") (class "Default")
      (node (ref "IC10") (pin "13") (pinfunction "11_13") (pintype "output"))
    )
    (net (code "144") (name "OUT12") (class "Default")
      (node (ref "IC10") (pin "14") (pinfunction "12_14") (pintype "output"))
    )
    (net (code "145") (name "OUT13") (class "Default")
      (node (ref "IC10") (pin "15") (pinfunction "13_15") (pintype "output"))
    )
    (net (code "146") (name "OUT14") (class "Default")
      (node (ref "IC10") (pin "16") (pinfunction "14_16") (pintype "output"))
    )
    (net (code "147") (name "OUT15") (class "Default")
      (node (ref "IC10") (pin "17") (pinfunction "15_17") (pintype "output"))
    )
    (net (code "148") (name "PIA-A0") (class "Default")
      (node (ref "IC1") (pin "3") (pinfunction "1D_3") (pintype "input"))
      (node (ref "IC11") (pin "2") (pinfunction "1Q_2") (pintype "tri_state"))
      (node (ref "IC12") (pin "2") (pinfunction "1Q_2") (pintype "tri_state"))
      (node (ref "IC13") (pin "2") (pinfunction "1Q_2") (pintype "tri_state"))
      (node (ref "IC14") (pin "2") (pinfunction "1Q_2") (pintype "tri_state"))
      (node (ref "IC15") (pin "2") (pinfunction "1Q_2") (pintype "tri_state"))
      (node (ref "IC16") (pin "2") (pinfunction "1Q_2") (pintype "tri_state"))
      (node (ref "IC2") (pin "3") (pinfunction "1D_3") (pintype "input"))
      (node (ref "IC3") (pin "3") (pinfunction "1D_3") (pintype "input"))
      (node (ref "IC4") (pin "3") (pinfunction "1D_3") (pintype "input"))
      (node (ref "IC5") (pin "3") (pinfunction "1D_3") (pintype "input"))
      (node (ref "IC6") (pin "3") (pinfunction "1D_3") (pintype "input"))
      (node (ref "IC7") (pin "3") (pinfunction "1D_3") (pintype "input"))
      (node (ref "IC8") (pin "3") (pinfunction "1D_3") (pintype "input"))
      (node (ref "SV9") (pin "1") (pinfunction "1_1") (pintype "passive"))
    )
    (net (code "149") (name "PIA-A1") (class "Default")
      (node (ref "IC1") (pin "4") (pinfunction "2D_4") (pintype "input"))
      (node (ref "IC11") (pin "5") (pinfunction "2Q_5") (pintype "tri_state"))
      (node (ref "IC12") (pin "5") (pinfunction "2Q_5") (pintype "tri_state"))
      (node (ref "IC13") (pin "5") (pinfunction "2Q_5") (pintype "tri_state"))
      (node (ref "IC14") (pin "5") (pinfunction "2Q_5") (pintype "tri_state"))
      (node (ref "IC15") (pin "5") (pinfunction "2Q_5") (pintype "tri_state"))
      (node (ref "IC16") (pin "5") (pinfunction "2Q_5") (pintype "tri_state"))
      (node (ref "IC2") (pin "4") (pinfunction "2D_4") (pintype "input"))
      (node (ref "IC3") (pin "4") (pinfunction "2D_4") (pintype "input"))
      (node (ref "IC4") (pin "4") (pinfunction "2D_4") (pintype "input"))
      (node (ref "IC5") (pin "4") (pinfunction "2D_4") (pintype "input"))
      (node (ref "IC6") (pin "4") (pinfunction "2D_4") (pintype "input"))
      (node (ref "IC7") (pin "4") (pinfunction "2D_4") (pintype "input"))
      (node (ref "IC8") (pin "4") (pinfunction "2D_4") (pintype "input"))
      (node (ref "SV9") (pin "2") (pinfunction "2_2") (pintype "passive"))
    )
    (net (code "150") (name "PIA-A2") (class "Default")
      (node (ref "IC1") (pin "7") (pinfunction "3D_7") (pintype "input"))
      (node (ref "IC11") (pin "6") (pinfunction "3Q_6") (pintype "tri_state"))
      (node (ref "IC12") (pin "6") (pinfunction "3Q_6") (pintype "tri_state"))
      (node (ref "IC13") (pin "6") (pinfunction "3Q_6") (pintype "tri_state"))
      (node (ref "IC14") (pin "6") (pinfunction "3Q_6") (pintype "tri_state"))
      (node (ref "IC15") (pin "6") (pinfunction "3Q_6") (pintype "tri_state"))
      (node (ref "IC16") (pin "6") (pinfunction "3Q_6") (pintype "tri_state"))
      (node (ref "IC2") (pin "7") (pinfunction "3D_7") (pintype "input"))
      (node (ref "IC3") (pin "7") (pinfunction "3D_7") (pintype "input"))
      (node (ref "IC4") (pin "7") (pinfunction "3D_7") (pintype "input"))
      (node (ref "IC5") (pin "7") (pinfunction "3D_7") (pintype "input"))
      (node (ref "IC6") (pin "7") (pinfunction "3D_7") (pintype "input"))
      (node (ref "IC7") (pin "7") (pinfunction "3D_7") (pintype "input"))
      (node (ref "IC8") (pin "7") (pinfunction "3D_7") (pintype "input"))
      (node (ref "SV9") (pin "3") (pinfunction "3_3") (pintype "passive"))
    )
    (net (code "151") (name "PIA-A3") (class "Default")
      (node (ref "IC1") (pin "8") (pinfunction "4D_8") (pintype "input"))
      (node (ref "IC11") (pin "9") (pinfunction "4Q_9") (pintype "tri_state"))
      (node (ref "IC12") (pin "9") (pinfunction "4Q_9") (pintype "tri_state"))
      (node (ref "IC13") (pin "9") (pinfunction "4Q_9") (pintype "tri_state"))
      (node (ref "IC14") (pin "9") (pinfunction "4Q_9") (pintype "tri_state"))
      (node (ref "IC15") (pin "9") (pinfunction "4Q_9") (pintype "tri_state"))
      (node (ref "IC16") (pin "9") (pinfunction "4Q_9") (pintype "tri_state"))
      (node (ref "IC2") (pin "8") (pinfunction "4D_8") (pintype "input"))
      (node (ref "IC3") (pin "8") (pinfunction "4D_8") (pintype "input"))
      (node (ref "IC4") (pin "8") (pinfunction "4D_8") (pintype "input"))
      (node (ref "IC5") (pin "8") (pinfunction "4D_8") (pintype "input"))
      (node (ref "IC6") (pin "8") (pinfunction "4D_8") (pintype "input"))
      (node (ref "IC7") (pin "8") (pinfunction "4D_8") (pintype "input"))
      (node (ref "IC8") (pin "8") (pinfunction "4D_8") (pintype "input"))
      (node (ref "SV9") (pin "4") (pinfunction "4_4") (pintype "passive"))
    )
    (net (code "152") (name "PIA-A4") (class "Default")
      (node (ref "IC1") (pin "13") (pinfunction "5D_13") (pintype "input"))
      (node (ref "IC11") (pin "12") (pinfunction "5Q_12") (pintype "tri_state"))
      (node (ref "IC12") (pin "12") (pinfunction "5Q_12") (pintype "tri_state"))
      (node (ref "IC13") (pin "12") (pinfunction "5Q_12") (pintype "tri_state"))
      (node (ref "IC14") (pin "12") (pinfunction "5Q_12") (pintype "tri_state"))
      (node (ref "IC15") (pin "12") (pinfunction "5Q_12") (pintype "tri_state"))
      (node (ref "IC16") (pin "12") (pinfunction "5Q_12") (pintype "tri_state"))
      (node (ref "IC2") (pin "13") (pinfunction "5D_13") (pintype "input"))
      (node (ref "IC3") (pin "13") (pinfunction "5D_13") (pintype "input"))
      (node (ref "IC4") (pin "13") (pinfunction "5D_13") (pintype "input"))
      (node (ref "IC5") (pin "13") (pinfunction "5D_13") (pintype "input"))
      (node (ref "IC6") (pin "13") (pinfunction "5D_13") (pintype "input"))
      (node (ref "IC7") (pin "13") (pinfunction "5D_13") (pintype "input"))
      (node (ref "IC8") (pin "13") (pinfunction "5D_13") (pintype "input"))
      (node (ref "SV9") (pin "5") (pinfunction "5_5") (pintype "passive"))
    )
    (net (code "153") (name "PIA-A5") (class "Default")
      (node (ref "IC1") (pin "14") (pinfunction "6D_14") (pintype "input"))
      (node (ref "IC11") (pin "15") (pinfunction "6Q_15") (pintype "tri_state"))
      (node (ref "IC12") (pin "15") (pinfunction "6Q_15") (pintype "tri_state"))
      (node (ref "IC13") (pin "15") (pinfunction "6Q_15") (pintype "tri_state"))
      (node (ref "IC14") (pin "15") (pinfunction "6Q_15") (pintype "tri_state"))
      (node (ref "IC15") (pin "15") (pinfunction "6Q_15") (pintype "tri_state"))
      (node (ref "IC16") (pin "15") (pinfunction "6Q_15") (pintype "tri_state"))
      (node (ref "IC2") (pin "14") (pinfunction "6D_14") (pintype "input"))
      (node (ref "IC3") (pin "14") (pinfunction "6D_14") (pintype "input"))
      (node (ref "IC4") (pin "14") (pinfunction "6D_14") (pintype "input"))
      (node (ref "IC5") (pin "14") (pinfunction "6D_14") (pintype "input"))
      (node (ref "IC6") (pin "14") (pinfunction "6D_14") (pintype "input"))
      (node (ref "IC7") (pin "14") (pinfunction "6D_14") (pintype "input"))
      (node (ref "IC8") (pin "14") (pinfunction "6D_14") (pintype "input"))
      (node (ref "SV9") (pin "6") (pinfunction "6_6") (pintype "passive"))
    )
    (net (code "154") (name "PIA-A6") (class "Default")
      (node (ref "IC1") (pin "17") (pinfunction "7D_17") (pintype "input"))
      (node (ref "IC11") (pin "16") (pinfunction "7Q_16") (pintype "tri_state"))
      (node (ref "IC12") (pin "16") (pinfunction "7Q_16") (pintype "tri_state"))
      (node (ref "IC13") (pin "16") (pinfunction "7Q_16") (pintype "tri_state"))
      (node (ref "IC14") (pin "16") (pinfunction "7Q_16") (pintype "tri_state"))
      (node (ref "IC15") (pin "16") (pinfunction "7Q_16") (pintype "tri_state"))
      (node (ref "IC16") (pin "16") (pinfunction "7Q_16") (pintype "tri_state"))
      (node (ref "IC2") (pin "17") (pinfunction "7D_17") (pintype "input"))
      (node (ref "IC3") (pin "17") (pinfunction "7D_17") (pintype "input"))
      (node (ref "IC4") (pin "17") (pinfunction "7D_17") (pintype "input"))
      (node (ref "IC5") (pin "17") (pinfunction "7D_17") (pintype "input"))
      (node (ref "IC6") (pin "17") (pinfunction "7D_17") (pintype "input"))
      (node (ref "IC7") (pin "17") (pinfunction "7D_17") (pintype "input"))
      (node (ref "IC8") (pin "17") (pinfunction "7D_17") (pintype "input"))
      (node (ref "SV9") (pin "7") (pinfunction "7_7") (pintype "passive"))
    )
    (net (code "155") (name "PIA-A7") (class "Default")
      (node (ref "IC1") (pin "18") (pinfunction "8D_18") (pintype "input"))
      (node (ref "IC11") (pin "19") (pinfunction "8Q_19") (pintype "tri_state"))
      (node (ref "IC12") (pin "19") (pinfunction "8Q_19") (pintype "tri_state"))
      (node (ref "IC13") (pin "19") (pinfunction "8Q_19") (pintype "tri_state"))
      (node (ref "IC14") (pin "19") (pinfunction "8Q_19") (pintype "tri_state"))
      (node (ref "IC15") (pin "19") (pinfunction "8Q_19") (pintype "tri_state"))
      (node (ref "IC16") (pin "19") (pinfunction "8Q_19") (pintype "tri_state"))
      (node (ref "IC2") (pin "18") (pinfunction "8D_18") (pintype "input"))
      (node (ref "IC3") (pin "18") (pinfunction "8D_18") (pintype "input"))
      (node (ref "IC4") (pin "18") (pinfunction "8D_18") (pintype "input"))
      (node (ref "IC5") (pin "18") (pinfunction "8D_18") (pintype "input"))
      (node (ref "IC6") (pin "18") (pinfunction "8D_18") (pintype "input"))
      (node (ref "IC7") (pin "18") (pinfunction "8D_18") (pintype "input"))
      (node (ref "IC8") (pin "18") (pinfunction "8D_18") (pintype "input"))
      (node (ref "SV9") (pin "8") (pinfunction "8_8") (pintype "passive"))
    )
    (net (code "156") (name "PIA-B0") (class "Default")
      (node (ref "IC10") (pin "23") (pinfunction "A_23") (pintype "input"))
      (node (ref "IC9") (pin "23") (pinfunction "A_23") (pintype "input"))
      (node (ref "SV9") (pin "13") (pinfunction "13_13") (pintype "passive"))
    )
    (net (code "157") (name "PIA-B1") (class "Default")
      (node (ref "IC10") (pin "22") (pinfunction "B_22") (pintype "input"))
      (node (ref "IC9") (pin "22") (pinfunction "B_22") (pintype "input"))
      (node (ref "SV9") (pin "14") (pinfunction "14_14") (pintype "passive"))
    )
    (net (code "158") (name "PIA-B2") (class "Default")
      (node (ref "IC10") (pin "21") (pinfunction "C_21") (pintype "input"))
      (node (ref "IC9") (pin "21") (pinfunction "C_21") (pintype "input"))
      (node (ref "SV9") (pin "15") (pinfunction "15_15") (pintype "passive"))
    )
    (net (code "159") (name "PIA-B3") (class "Default")
      (node (ref "IC10") (pin "20") (pinfunction "D_20") (pintype "input"))
      (node (ref "IC9") (pin "20") (pinfunction "D_20") (pintype "input"))
      (node (ref "SV9") (pin "16") (pinfunction "16_16") (pintype "passive"))
    )
    (net (code "160") (name "PIA-B4") (class "Default")
      (node (ref "JP1") (pin "1") (pinfunction "1_1") (pintype "passive"))
      (node (ref "SV9") (pin "17") (pinfunction "17_17") (pintype "passive"))
    )
    (net (code "161") (name "PIA-B5") (class "Default")
      (node (ref "JP1") (pin "2") (pinfunction "2_2") (pintype "passive"))
      (node (ref "SV9") (pin "18") (pinfunction "18_18") (pintype "passive"))
    )
    (net (code "162") (name "PIA-B6") (class "Default")
      (node (ref "JP1") (pin "5") (pinfunction "5_5") (pintype "passive"))
      (node (ref "SV9") (pin "19") (pinfunction "19_19") (pintype "passive"))
    )
    (net (code "163") (name "PIA-B7") (class "Default")
      (node (ref "JP1") (pin "6") (pinfunction "6_6") (pintype "passive"))
      (node (ref "SV9") (pin "20") (pinfunction "20_20") (pintype "passive"))
    )
    (net (code "164") (name "VCC") (class "Default")
      (node (ref "BYP1") (pin "1") (pinfunction "1_1") (pintype "passive"))
      (node (ref "BYP10") (pin "1") (pinfunction "1_1") (pintype "passive"))
      (node (ref "BYP11") (pin "1") (pinfunction "1_1") (pintype "passive"))
      (node (ref "BYP12") (pin "1") (pinfunction "1_1") (pintype "passive"))
      (node (ref "BYP13") (pin "1") (pinfunction "1_1") (pintype "passive"))
      (node (ref "BYP14") (pin "1") (pinfunction "1_1") (pintype "passive"))
      (node (ref "BYP15") (pin "1") (pinfunction "1_1") (pintype "passive"))
      (node (ref "BYP16") (pin "1") (pinfunction "1_1") (pintype "passive"))
      (node (ref "BYP2") (pin "1") (pinfunction "1_1") (pintype "passive"))
      (node (ref "BYP3") (pin "1") (pinfunction "1_1") (pintype "passive"))
      (node (ref "BYP4") (pin "1") (pinfunction "1_1") (pintype "passive"))
      (node (ref "BYP5") (pin "1") (pinfunction "1_1") (pintype "passive"))
      (node (ref "BYP6") (pin "1") (pinfunction "1_1") (pintype "passive"))
      (node (ref "BYP7") (pin "1") (pinfunction "1_1") (pintype "passive"))
      (node (ref "BYP8") (pin "1") (pinfunction "1_1") (pintype "passive"))
      (node (ref "BYP9") (pin "1") (pinfunction "1_1") (pintype "passive"))
      (node (ref "IC11") (pin "11") (pinfunction "ENC_11") (pintype "input"))
      (node (ref "IC12") (pin "11") (pinfunction "ENC_11") (pintype "input"))
      (node (ref "IC13") (pin "11") (pinfunction "ENC_11") (pintype "input"))
      (node (ref "IC14") (pin "11") (pinfunction "ENC_11") (pintype "input"))
      (node (ref "IC15") (pin "11") (pinfunction "ENC_11") (pintype "input"))
      (node (ref "IC16") (pin "11") (pinfunction "ENC_11") (pintype "input"))
      (node (ref "SV9") (pin "11") (pinfunction "11_11") (pintype "passive"))
      (node (ref "SV9") (pin "12") (pinfunction "12_12") (pintype "passive"))
    )
  )
)
